# Flash.net
KiCad netlist of a schematic drawn in Altium Designer
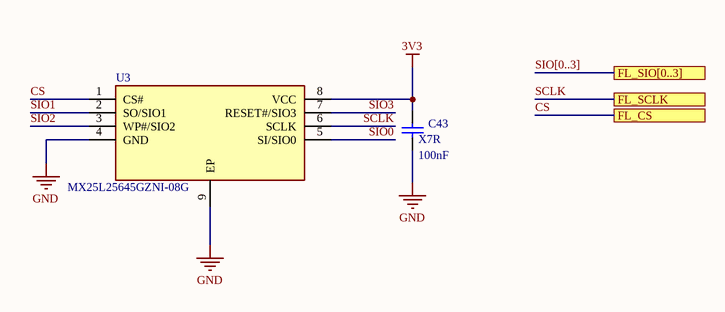
[diagram p0: Flash.SchDoc]

(export (version "E")
  (design (tool "Eeschema 10.0.6"))
  (components
    (comp (ref "C43")
      (value "X7R")
      (footprint "1608[0603]")
      (description "Capacitor")
      (fields (field (name "ALTIUM_VALUE") "100nF") (field (name "PUBLISHER") "Altium Limited"))
      (libsource (lib "Miscellaneous Devices") (part "Cap"))
    )
    (comp (ref "U3")
      (value "MX25L25645GZNI-08G")
      (footprint "SamacSys:SON127P600X500X80-9N-D")
      (description "Integrated Circuit")
      (libsource (lib "*") (part "MX25L25645GZNI-08G"))
    )
  )
  (nets
    (net (code "1") (name "/CS") (class "Default")
      (node (ref "U3") (pin "1") (pinfunction "CS#_1") (pintype "passive"))
    )
    (net (code "2") (name "/SCLK") (class "Default")
      (node (ref "U3") (pin "6") (pinfunction "SCLK_6") (pintype "passive"))
    )
    (net (code "3") (name "/SIO0") (class "Default")
      (node (ref "U3") (pin "5") (pinfunction "SI/SIO0_5") (pintype "passive"))
    )
    (net (code "4") (name "/SIO1") (class "Default")
      (node (ref "U3") (pin "2") (pinfunction "SO/SIO1_2") (pintype "passive"))
    )
    (net (code "5") (name "/SIO2") (class "Default")
      (node (ref "U3") (pin "3") (pinfunction "WP#/SIO2_3") (pintype "passive"))
    )
    (net (code "6") (name "/SIO3") (class "Default")
      (node (ref "U3") (pin "7") (pinfunction "RESET#/SIO3_7") (pintype "passive"))
    )
    (net (code "8") (name "3V3") (class "Default")
      (node (ref "C43") (pin "2") (pinfunction "2_2") (pintype "passive"))
      (node (ref "U3") (pin "8") (pinfunction "VCC_8") (pintype "passive"))
    )
    (net (code "9") (name "GND") (class "Default")
      (node (ref "C43") (pin "1") (pinfunction "1_1") (pintype "passive"))
      (node (ref "U3") (pin "4") (pinfunction "GND_4") (pintype "passive"))
      (node (ref "U3") (pin "9") (pinfunction "EP_9") (pintype "passive"))
    )
  )
)
